# MainBlock-Inputs.net
KiCad netlist of a schematic drawn in Altium Designer
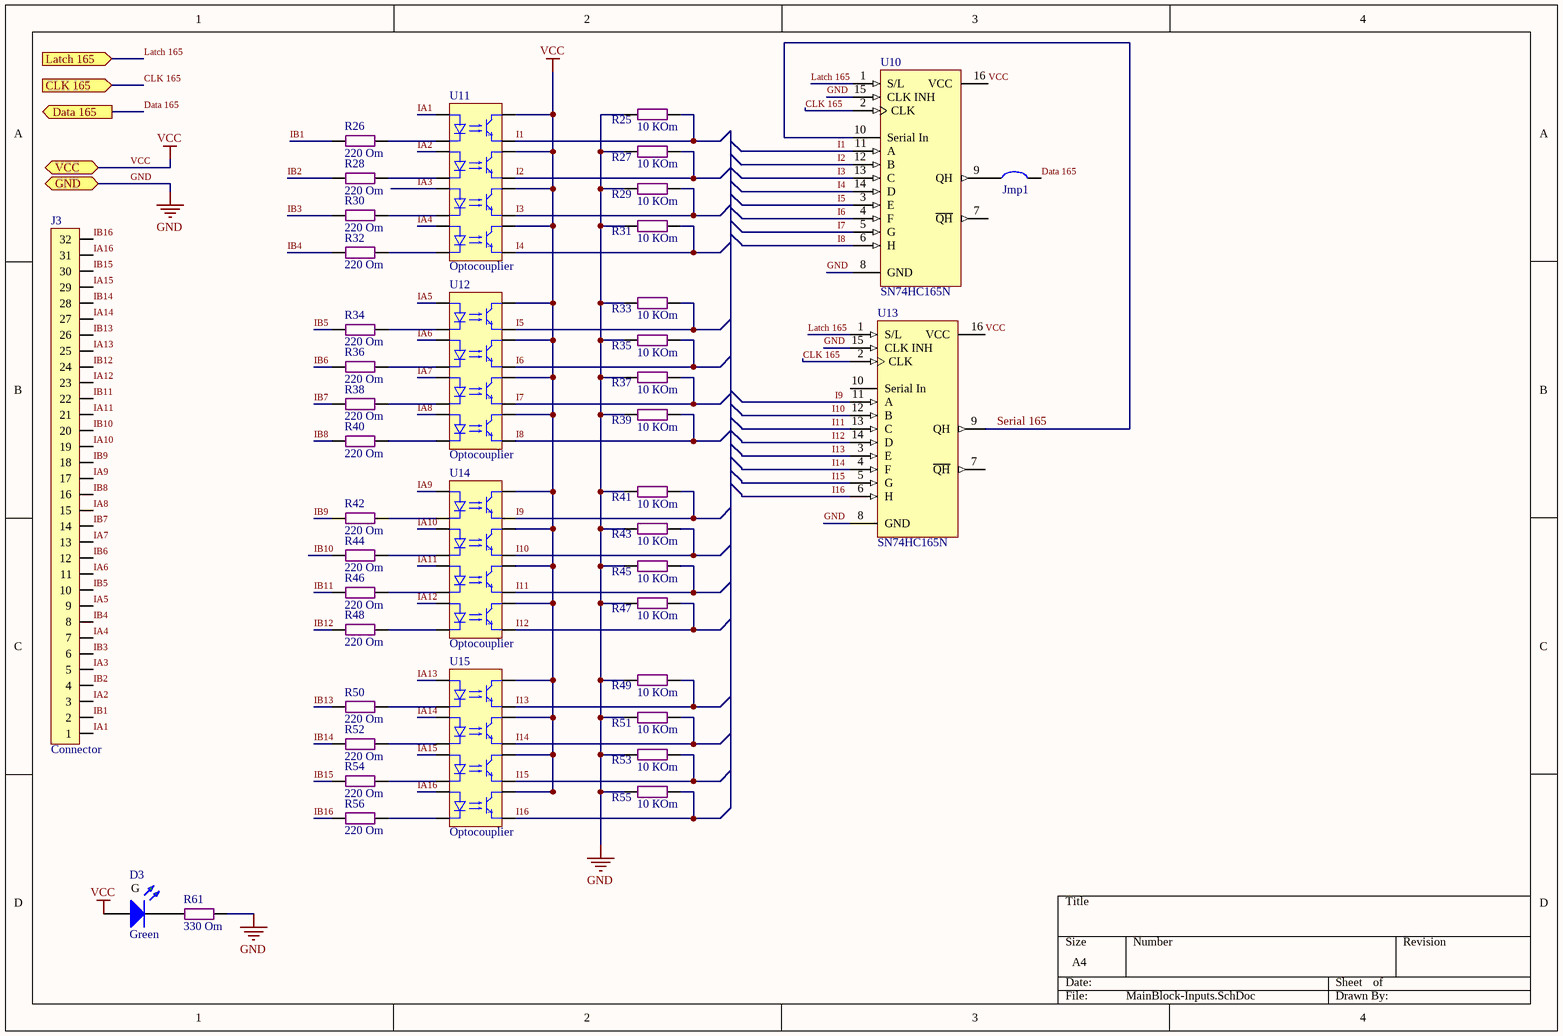
[diagram p0: MainBlock-Inputs.SchDoc]

(export (version "E")
  (design (tool "Eeschema 10.0.6"))
  (components
    (comp (ref "D3")
      (value "Green")
      (footprint "LED:LED SMD 0805 Green")
      (description "?2v ?20mA")
      (libsource (lib "LED") (part "Led SMD 0805 Green"))
    )
    (comp (ref "J3")
      (value "Connector")
      (footprint "bj Lib:LINE 2.54 x 16D")
      (description "32pin Connector")
      (libsource (lib "ss_ServersControl") (part "Connector Dbl ( 32 pin )"))
    )
    (comp (ref "Jmp1")
      (value "Jumper")
      (footprint "bj Lib:Jumper S 13x4")
      (libsource (lib "ss_ServersControl") (part "Jumper"))
    )
    (comp (ref "R25")
      (value "10 КOm")
      (footprint "SMD 0603 (1608)")
      (libsource (lib "ss_ServersControl") (part "Resistor"))
    )
    (comp (ref "R26")
      (value "220 Om")
      (footprint "bj Lib:SMD 1206 (3216)")
      (libsource (lib "ss_ServersControl") (part "Resistor"))
    )
    (comp (ref "R27")
      (value "10 КOm")
      (footprint "SMD 0603 (1608)")
      (libsource (lib "ss_ServersControl") (part "Resistor"))
    )
    (comp (ref "R28")
      (value "220 Om")
      (footprint "bj Lib:SMD 1206 (3216)")
      (libsource (lib "ss_ServersControl") (part "Resistor"))
    )
    (comp (ref "R29")
      (value "10 КOm")
      (footprint "SMD 0603 (1608)")
      (libsource (lib "ss_ServersControl") (part "Resistor"))
    )
    (comp (ref "R30")
      (value "220 Om")
      (footprint "bj Lib:SMD 1206 (3216)")
      (libsource (lib "ss_ServersControl") (part "Resistor"))
    )
    (comp (ref "R31")
      (value "10 КOm")
      (footprint "SMD 0603 (1608)")
      (libsource (lib "ss_ServersControl") (part "Resistor"))
    )
    (comp (ref "R32")
      (value "220 Om")
      (footprint "bj Lib:SMD 1206 (3216)")
      (libsource (lib "ss_ServersControl") (part "Resistor"))
    )
    (comp (ref "R33")
      (value "10 КOm")
      (footprint "SMD 0603 (1608)")
      (libsource (lib "ss_ServersControl") (part "Resistor"))
    )
    (comp (ref "R34")
      (value "220 Om")
      (footprint "bj Lib:SMD 1206 (3216)")
      (libsource (lib "ss_ServersControl") (part "Resistor"))
    )
    (comp (ref "R35")
      (value "10 КOm")
      (footprint "SMD 0603 (1608)")
      (libsource (lib "ss_ServersControl") (part "Resistor"))
    )
    (comp (ref "R36")
      (value "220 Om")
      (footprint "bj Lib:SMD 1206 (3216)")
      (libsource (lib "ss_ServersControl") (part "Resistor"))
    )
    (comp (ref "R37")
      (value "10 КOm")
      (footprint "SMD 0603 (1608)")
      (libsource (lib "ss_ServersControl") (part "Resistor"))
    )
    (comp (ref "R38")
      (value "220 Om")
      (footprint "bj Lib:SMD 1206 (3216)")
      (libsource (lib "ss_ServersControl") (part "Resistor"))
    )
    (comp (ref "R39")
      (value "10 КOm")
      (footprint "SMD 0603 (1608)")
      (libsource (lib "ss_ServersControl") (part "Resistor"))
    )
    (comp (ref "R40")
      (value "220 Om")
      (footprint "bj Lib:SMD 1206 (3216)")
      (libsource (lib "ss_ServersControl") (part "Resistor"))
    )
    (comp (ref "R41")
      (value "10 КOm")
      (footprint "SMD 0603 (1608)")
      (libsource (lib "ss_ServersControl") (part "Resistor"))
    )
    (comp (ref "R42")
      (value "220 Om")
      (footprint "Res p7.62 (4p)")
      (libsource (lib "ss_ServersControl") (part "Resistor"))
    )
    (comp (ref "R43")
      (value "10 КOm")
      (footprint "SMD 0603 (1608)")
      (libsource (lib "ss_ServersControl") (part "Resistor"))
    )
    (comp (ref "R44")
      (value "220 Om")
      (footprint "Res p7.62 (4p)")
      (libsource (lib "ss_ServersControl") (part "Resistor"))
    )
    (comp (ref "R45")
      (value "10 КOm")
      (footprint "SMD 0603 (1608)")
      (libsource (lib "ss_ServersControl") (part "Resistor"))
    )
    (comp (ref "R46")
      (value "220 Om")
      (footprint "Res p7.62 (4p)")
      (libsource (lib "ss_ServersControl") (part "Resistor"))
    )
    (comp (ref "R47")
      (value "10 КOm")
      (footprint "SMD 0603 (1608)")
      (libsource (lib "ss_ServersControl") (part "Resistor"))
    )
    (comp (ref "R48")
      (value "220 Om")
      (footprint "Res p7.62 (4p)")
      (libsource (lib "ss_ServersControl") (part "Resistor"))
    )
    (comp (ref "R49")
      (value "10 КOm")
      (footprint "SMD 0603 (1608)")
      (libsource (lib "ss_ServersControl") (part "Resistor"))
    )
    (comp (ref "R50")
      (value "220 Om")
      (footprint "bj Lib:SMD 1206 (3216)")
      (libsource (lib "ss_ServersControl") (part "Resistor"))
    )
    (comp (ref "R51")
      (value "10 КOm")
      (footprint "SMD 0603 (1608)")
      (libsource (lib "ss_ServersControl") (part "Resistor"))
    )
    (comp (ref "R52")
      (value "220 Om")
      (footprint "bj Lib:SMD 1206 (3216)")
      (libsource (lib "ss_ServersControl") (part "Resistor"))
    )
    (comp (ref "R53")
      (value "10 КOm")
      (footprint "SMD 0603 (1608)")
      (libsource (lib "ss_ServersControl") (part "Resistor"))
    )
    (comp (ref "R54")
      (value "220 Om")
      (footprint "bj Lib:SMD 1206 (3216)")
      (libsource (lib "ss_ServersControl") (part "Resistor"))
    )
    (comp (ref "R55")
      (value "10 КOm")
      (footprint "SMD 0603 (1608)")
      (libsource (lib "ss_ServersControl") (part "Resistor"))
    )
    (comp (ref "R56")
      (value "220 Om")
      (footprint "bj Lib:SMD 1206 (3216)")
      (libsource (lib "ss_ServersControl") (part "Resistor"))
    )
    (comp (ref "R61")
      (value "330 Om")
      (footprint "bj Lib:SMD 0603 (1608)")
      (libsource (lib "ss_ServersControl") (part "Resistor"))
    )
    (comp (ref "U10")
      (value "SN74HC165N")
      (footprint "bj Lib:DIP16")
      (description "8-Bit Parallel-Load Shift Register")
      (fields (field (name "PUBLISHER") "Altium Limited"))
      (libsource (lib "ss_ServersControl") (part "SN74HC165N"))
    )
    (comp (ref "U11")
      (value "Optocouplier")
      (footprint "bj Lib:DIP16")
      (description "4x channel")
      (libsource (lib "bj Lib") (part "Optocouplier 4x"))
    )
    (comp (ref "U12")
      (value "Optocouplier")
      (footprint "bj Lib:DIP16")
      (description "4x channel")
      (libsource (lib "bj Lib") (part "Optocouplier 4x"))
    )
    (comp (ref "U13")
      (value "SN74HC165N")
      (footprint "bj Lib:DIP16")
      (description "8-Bit Parallel-Load Shift Register")
      (fields (field (name "PUBLISHER") "Altium Limited"))
      (libsource (lib "ss_ServersControl") (part "SN74HC165N"))
    )
    (comp (ref "U14")
      (value "Optocouplier")
      (footprint "bj Lib:DIP16")
      (description "4x channel")
      (libsource (lib "bj Lib") (part "Optocouplier 4x"))
    )
    (comp (ref "U15")
      (value "Optocouplier")
      (footprint "bj Lib:DIP16")
      (description "4x channel")
      (libsource (lib "bj Lib") (part "Optocouplier 4x"))
    )
  )
  (nets
    (net (code "1") (name "/CLK 165") (class "Default")
      (node (ref "U10") (pin "2") (pinfunction "CLK_2") (pintype "input"))
      (node (ref "U13") (pin "2") (pinfunction "CLK_2") (pintype "input"))
    )
    (net (code "2") (name "/Data 165") (class "Default")
      (node (ref "Jmp1") (pin "2") (pinfunction "2_2") (pintype "passive"))
    )
    (net (code "3") (name "/I1") (class "Default")
      (node (ref "R25") (pin "2") (pinfunction "2_2") (pintype "passive"))
      (node (ref "U10") (pin "11") (pinfunction "A_11") (pintype "input"))
      (node (ref "U11") (pin "15") (pinfunction "15_15") (pintype "passive"))
    )
    (net (code "4") (name "/I2") (class "Default")
      (node (ref "R27") (pin "2") (pinfunction "2_2") (pintype "passive"))
      (node (ref "U10") (pin "12") (pinfunction "B_12") (pintype "input"))
      (node (ref "U11") (pin "13") (pinfunction "13_13") (pintype "passive"))
    )
    (net (code "5") (name "/I3") (class "Default")
      (node (ref "R29") (pin "2") (pinfunction "2_2") (pintype "passive"))
      (node (ref "U10") (pin "13") (pinfunction "C_13") (pintype "input"))
      (node (ref "U11") (pin "11") (pinfunction "11_11") (pintype "passive"))
    )
    (net (code "6") (name "/I4") (class "Default")
      (node (ref "R31") (pin "2") (pinfunction "2_2") (pintype "passive"))
      (node (ref "U10") (pin "14") (pinfunction "D_14") (pintype "input"))
      (node (ref "U11") (pin "9") (pinfunction "9_9") (pintype "passive"))
    )
    (net (code "7") (name "/I5") (class "Default")
      (node (ref "R33") (pin "2") (pinfunction "2_2") (pintype "passive"))
      (node (ref "U10") (pin "3") (pinfunction "E_3") (pintype "input"))
      (node (ref "U12") (pin "15") (pinfunction "15_15") (pintype "passive"))
    )
    (net (code "8") (name "/I6") (class "Default")
      (node (ref "R35") (pin "2") (pinfunction "2_2") (pintype "passive"))
      (node (ref "U10") (pin "4") (pinfunction "F_4") (pintype "input"))
      (node (ref "U12") (pin "13") (pinfunction "13_13") (pintype "passive"))
    )
    (net (code "9") (name "/I7") (class "Default")
      (node (ref "R37") (pin "2") (pinfunction "2_2") (pintype "passive"))
      (node (ref "U10") (pin "5") (pinfunction "G_5") (pintype "input"))
      (node (ref "U12") (pin "11") (pinfunction "11_11") (pintype "passive"))
    )
    (net (code "10") (name "/I8") (class "Default")
      (node (ref "R39") (pin "2") (pinfunction "2_2") (pintype "passive"))
      (node (ref "U10") (pin "6") (pinfunction "H_6") (pintype "input"))
      (node (ref "U12") (pin "9") (pinfunction "9_9") (pintype "passive"))
    )
    (net (code "11") (name "/I9") (class "Default")
      (node (ref "R41") (pin "2") (pinfunction "2_2") (pintype "passive"))
      (node (ref "U13") (pin "11") (pinfunction "A_11") (pintype "input"))
      (node (ref "U14") (pin "15") (pinfunction "15_15") (pintype "passive"))
    )
    (net (code "12") (name "/I10") (class "Default")
      (node (ref "R43") (pin "2") (pinfunction "2_2") (pintype "passive"))
      (node (ref "U13") (pin "12") (pinfunction "B_12") (pintype "input"))
      (node (ref "U14") (pin "13") (pinfunction "13_13") (pintype "passive"))
    )
    (net (code "13") (name "/I11") (class "Default")
      (node (ref "R45") (pin "2") (pinfunction "2_2") (pintype "passive"))
      (node (ref "U13") (pin "13") (pinfunction "C_13") (pintype "input"))
      (node (ref "U14") (pin "11") (pinfunction "11_11") (pintype "passive"))
    )
    (net (code "14") (name "/I12") (class "Default")
      (node (ref "R47") (pin "2") (pinfunction "2_2") (pintype "passive"))
      (node (ref "U13") (pin "14") (pinfunction "D_14") (pintype "input"))
      (node (ref "U14") (pin "9") (pinfunction "9_9") (pintype "passive"))
    )
    (net (code "15") (name "/I13") (class "Default")
      (node (ref "R49") (pin "2") (pinfunction "2_2") (pintype "passive"))
      (node (ref "U13") (pin "3") (pinfunction "E_3") (pintype "input"))
      (node (ref "U15") (pin "15") (pinfunction "15_15") (pintype "passive"))
    )
    (net (code "16") (name "/I14") (class "Default")
      (node (ref "R51") (pin "2") (pinfunction "2_2") (pintype "passive"))
      (node (ref "U13") (pin "4") (pinfunction "F_4") (pintype "input"))
      (node (ref "U15") (pin "13") (pinfunction "13_13") (pintype "passive"))
    )
    (net (code "17") (name "/I15") (class "Default")
      (node (ref "R53") (pin "2") (pinfunction "2_2") (pintype "passive"))
      (node (ref "U13") (pin "5") (pinfunction "G_5") (pintype "input"))
      (node (ref "U15") (pin "11") (pinfunction "11_11") (pintype "passive"))
    )
    (net (code "18") (name "/I16") (class "Default")
      (node (ref "R55") (pin "2") (pinfunction "2_2") (pintype "passive"))
      (node (ref "U13") (pin "6") (pinfunction "H_6") (pintype "input"))
      (node (ref "U15") (pin "9") (pinfunction "9_9") (pintype "passive"))
    )
    (net (code "19") (name "/IA1") (class "Default")
      (node (ref "J3") (pin "1") (pinfunction "1_1") (pintype "passive"))
      (node (ref "U11") (pin "1") (pinfunction "1_1") (pintype "passive"))
    )
    (net (code "20") (name "/IA2") (class "Default")
      (node (ref "J3") (pin "3") (pinfunction "3_3") (pintype "passive"))
      (node (ref "U11") (pin "3") (pinfunction "3_3") (pintype "passive"))
    )
    (net (code "21") (name "/IA3") (class "Default")
      (node (ref "J3") (pin "5") (pinfunction "5_5") (pintype "passive"))
      (node (ref "U11") (pin "5") (pinfunction "5_5") (pintype "passive"))
    )
    (net (code "22") (name "/IA4") (class "Default")
      (node (ref "J3") (pin "7") (pinfunction "7_7") (pintype "passive"))
      (node (ref "U11") (pin "7") (pinfunction "7_7") (pintype "passive"))
    )
    (net (code "23") (name "/IA5") (class "Default")
      (node (ref "J3") (pin "9") (pinfunction "9_9") (pintype "passive"))
      (node (ref "U12") (pin "1") (pinfunction "1_1") (pintype "passive"))
    )
    (net (code "24") (name "/IA6") (class "Default")
      (node (ref "J3") (pin "11") (pinfunction "11_11") (pintype "passive"))
      (node (ref "U12") (pin "3") (pinfunction "3_3") (pintype "passive"))
    )
    (net (code "25") (name "/IA7") (class "Default")
      (node (ref "J3") (pin "13") (pinfunction "13_13") (pintype "passive"))
      (node (ref "U12") (pin "5") (pinfunction "5_5") (pintype "passive"))
    )
    (net (code "26") (name "/IA8") (class "Default")
      (node (ref "J3") (pin "15") (pinfunction "15_15") (pintype "passive"))
      (node (ref "U12") (pin "7") (pinfunction "7_7") (pintype "passive"))
    )
    (net (code "27") (name "/IA9") (class "Default")
      (node (ref "J3") (pin "17") (pinfunction "17_17") (pintype "passive"))
      (node (ref "U14") (pin "1") (pinfunction "1_1") (pintype "passive"))
    )
    (net (code "28") (name "/IA10") (class "Default")
      (node (ref "J3") (pin "19") (pinfunction "19_19") (pintype "passive"))
      (node (ref "U14") (pin "3") (pinfunction "3_3") (pintype "passive"))
    )
    (net (code "29") (name "/IA11") (class "Default")
      (node (ref "J3") (pin "21") (pinfunction "21_21") (pintype "passive"))
      (node (ref "U14") (pin "5") (pinfunction "5_5") (pintype "passive"))
    )
    (net (code "30") (name "/IA12") (class "Default")
      (node (ref "J3") (pin "23") (pinfunction "23_23") (pintype "passive"))
      (node (ref "U14") (pin "7") (pinfunction "7_7") (pintype "passive"))
    )
    (net (code "31") (name "/IA13") (class "Default")
      (node (ref "J3") (pin "25") (pinfunction "25_25") (pintype "passive"))
      (node (ref "U15") (pin "1") (pinfunction "1_1") (pintype "passive"))
    )
    (net (code "32") (name "/IA14") (class "Default")
      (node (ref "J3") (pin "27") (pinfunction "27_27") (pintype "passive"))
      (node (ref "U15") (pin "3") (pinfunction "3_3") (pintype "passive"))
    )
    (net (code "33") (name "/IA15") (class "Default")
      (node (ref "J3") (pin "29") (pinfunction "29_29") (pintype "passive"))
      (node (ref "U15") (pin "5") (pinfunction "5_5") (pintype "passive"))
    )
    (net (code "34") (name "/IA16") (class "Default")
      (node (ref "J3") (pin "31") (pinfunction "31_31") (pintype "passive"))
      (node (ref "U15") (pin "7") (pinfunction "7_7") (pintype "passive"))
    )
    (net (code "35") (name "/IB1") (class "Default")
      (node (ref "J3") (pin "2") (pinfunction "2_2") (pintype "passive"))
      (node (ref "R26") (pin "1") (pinfunction "1_1") (pintype "passive"))
    )
    (net (code "36") (name "/IB2") (class "Default")
      (node (ref "J3") (pin "4") (pinfunction "4_4") (pintype "passive"))
      (node (ref "R28") (pin "1") (pinfunction "1_1") (pintype "passive"))
    )
    (net (code "37") (name "/IB3") (class "Default")
      (node (ref "J3") (pin "6") (pinfunction "6_6") (pintype "passive"))
      (node (ref "R30") (pin "1") (pinfunction "1_1") (pintype "passive"))
    )
    (net (code "38") (name "/IB4") (class "Default")
      (node (ref "J3") (pin "8") (pinfunction "8_8") (pintype "passive"))
      (node (ref "R32") (pin "1") (pinfunction "1_1") (pintype "passive"))
    )
    (net (code "39") (name "/IB5") (class "Default")
      (node (ref "J3") (pin "10") (pinfunction "10_10") (pintype "passive"))
      (node (ref "R34") (pin "1") (pinfunction "1_1") (pintype "passive"))
    )
    (net (code "40") (name "/IB6") (class "Default")
      (node (ref "J3") (pin "12") (pinfunction "12_12") (pintype "passive"))
      (node (ref "R36") (pin "1") (pinfunction "1_1") (pintype "passive"))
    )
    (net (code "41") (name "/IB7") (class "Default")
      (node (ref "J3") (pin "14") (pinfunction "14_14") (pintype "passive"))
      (node (ref "R38") (pin "1") (pinfunction "1_1") (pintype "passive"))
    )
    (net (code "42") (name "/IB8") (class "Default")
      (node (ref "J3") (pin "16") (pinfunction "16_16") (pintype "passive"))
      (node (ref "R40") (pin "1") (pinfunction "1_1") (pintype "passive"))
    )
    (net (code "43") (name "/IB9") (class "Default")
      (node (ref "J3") (pin "18") (pinfunction "18_18") (pintype "passive"))
      (node (ref "R42") (pin "1") (pinfunction "1_1") (pintype "passive"))
    )
    (net (code "44") (name "/IB10") (class "Default")
      (node (ref "J3") (pin "20") (pinfunction "20_20") (pintype "passive"))
      (node (ref "R44") (pin "1") (pinfunction "1_1") (pintype "passive"))
    )
    (net (code "45") (name "/IB11") (class "Default")
      (node (ref "J3") (pin "22") (pinfunction "22_22") (pintype "passive"))
      (node (ref "R46") (pin "1") (pinfunction "1_1") (pintype "passive"))
    )
    (net (code "46") (name "/IB12") (class "Default")
      (node (ref "J3") (pin "24") (pinfunction "24_24") (pintype "passive"))
      (node (ref "R48") (pin "1") (pinfunction "1_1") (pintype "passive"))
    )
    (net (code "47") (name "/IB13") (class "Default")
      (node (ref "J3") (pin "26") (pinfunction "26_26") (pintype "passive"))
      (node (ref "R50") (pin "1") (pinfunction "1_1") (pintype "passive"))
    )
    (net (code "48") (name "/IB14") (class "Default")
      (node (ref "J3") (pin "28") (pinfunction "28_28") (pintype "passive"))
      (node (ref "R52") (pin "1") (pinfunction "1_1") (pintype "passive"))
    )
    (net (code "49") (name "/IB15") (class "Default")
      (node (ref "J3") (pin "30") (pinfunction "30_30") (pintype "passive"))
      (node (ref "R54") (pin "1") (pinfunction "1_1") (pintype "passive"))
    )
    (net (code "50") (name "/IB16") (class "Default")
      (node (ref "J3") (pin "32") (pinfunction "32_32") (pintype "passive"))
      (node (ref "R56") (pin "1") (pinfunction "1_1") (pintype "passive"))
    )
    (net (code "51") (name "/Latch 165") (class "Default")
      (node (ref "U10") (pin "1") (pinfunction "S/L_1") (pintype "input"))
      (node (ref "U13") (pin "1") (pinfunction "S/L_1") (pintype "input"))
    )
    (net (code "52") (name "/Serial 165") (class "Default")
      (node (ref "U10") (pin "10") (pinfunction "Serial_In_10") (pintype "passive"))
      (node (ref "U13") (pin "9") (pinfunction "QH_9") (pintype "output"))
    )
    (net (code "53") (name "GND") (class "Default")
      (node (ref "R25") (pin "1") (pinfunction "1_1") (pintype "passive"))
      (node (ref "R27") (pin "1") (pinfunction "1_1") (pintype "passive"))
      (node (ref "R29") (pin "1") (pinfunction "1_1") (pintype "passive"))
      (node (ref "R31") (pin "1") (pinfunction "1_1") (pintype "passive"))
      (node (ref "R33") (pin "1") (pinfunction "1_1") (pintype "passive"))
      (node (ref "R35") (pin "1") (pinfunction "1_1") (pintype "passive"))
      (node (ref "R37") (pin "1") (pinfunction "1_1") (pintype "passive"))
      (node (ref "R39") (pin "1") (pinfunction "1_1") (pintype "passive"))
      (node (ref "R41") (pin "1") (pinfunction "1_1") (pintype "passive"))
      (node (ref "R43") (pin "1") (pinfunction "1_1") (pintype "passive"))
      (node (ref "R45") (pin "1") (pinfunction "1_1") (pintype "passive"))
      (node (ref "R47") (pin "1") (pinfunction "1_1") (pintype "passive"))
      (node (ref "R49") (pin "1") (pinfunction "1_1") (pintype "passive"))
      (node (ref "R51") (pin "1") (pinfunction "1_1") (pintype "passive"))
      (node (ref "R53") (pin "1") (pinfunction "1_1") (pintype "passive"))
      (node (ref "R55") (pin "1") (pinfunction "1_1") (pintype "passive"))
      (node (ref "R61") (pin "2") (pinfunction "2_2") (pintype "passive"))
      (node (ref "U10") (pin "15") (pinfunction "CLK_INH_15") (pintype "input"))
      (node (ref "U10") (pin "8") (pinfunction "GND_8") (pintype "power_in"))
      (node (ref "U13") (pin "15") (pinfunction "CLK_INH_15") (pintype "input"))
      (node (ref "U13") (pin "8") (pinfunction "GND_8") (pintype "power_in"))
    )
    (net (code "54") (name "Net-(D3-PadK)") (class "Default")
      (node (ref "D3") (pin "K") (pinfunction "K_K") (pintype "passive"))
      (node (ref "R61") (pin "1") (pinfunction "1_1") (pintype "passive"))
    )
    (net (code "55") (name "Net-(R26-Pad2)") (class "Default")
      (node (ref "R26") (pin "2") (pinfunction "2_2") (pintype "passive"))
      (node (ref "U11") (pin "2") (pinfunction "2_2") (pintype "passive"))
    )
    (net (code "56") (name "Net-(R28-Pad2)") (class "Default")
      (node (ref "R28") (pin "2") (pinfunction "2_2") (pintype "passive"))
      (node (ref "U11") (pin "4") (pinfunction "4_4") (pintype "passive"))
    )
    (net (code "57") (name "Net-(R30-Pad2)") (class "Default")
      (node (ref "R30") (pin "2") (pinfunction "2_2") (pintype "passive"))
      (node (ref "U11") (pin "6") (pinfunction "6_6") (pintype "passive"))
    )
    (net (code "58") (name "Net-(R32-Pad2)") (class "Default")
      (node (ref "R32") (pin "2") (pinfunction "2_2") (pintype "passive"))
      (node (ref "U11") (pin "8") (pinfunction "8_8") (pintype "passive"))
    )
    (net (code "59") (name "Net-(R34-Pad2)") (class "Default")
      (node (ref "R34") (pin "2") (pinfunction "2_2") (pintype "passive"))
      (node (ref "U12") (pin "2") (pinfunction "2_2") (pintype "passive"))
    )
    (net (code "60") (name "Net-(R36-Pad2)") (class "Default")
      (node (ref "R36") (pin "2") (pinfunction "2_2") (pintype "passive"))
      (node (ref "U12") (pin "4") (pinfunction "4_4") (pintype "passive"))
    )
    (net (code "61") (name "Net-(R38-Pad2)") (class "Default")
      (node (ref "R38") (pin "2") (pinfunction "2_2") (pintype "passive"))
      (node (ref "U12") (pin "6") (pinfunction "6_6") (pintype "passive"))
    )
    (net (code "62") (name "Net-(R40-Pad2)") (class "Default")
      (node (ref "R40") (pin "2") (pinfunction "2_2") (pintype "passive"))
      (node (ref "U12") (pin "8") (pinfunction "8_8") (pintype "passive"))
    )
    (net (code "63") (name "Net-(R42-Pad2)") (class "Default")
      (node (ref "R42") (pin "2") (pinfunction "2_2") (pintype "passive"))
      (node (ref "U14") (pin "2") (pinfunction "2_2") (pintype "passive"))
    )
    (net (code "64") (name "Net-(R44-Pad2)") (class "Default")
      (node (ref "R44") (pin "2") (pinfunction "2_2") (pintype "passive"))
      (node (ref "U14") (pin "4") (pinfunction "4_4") (pintype "passive"))
    )
    (net (code "65") (name "Net-(R46-Pad2)") (class "Default")
      (node (ref "R46") (pin "2") (pinfunction "2_2") (pintype "passive"))
      (node (ref "U14") (pin "6") (pinfunction "6_6") (pintype "passive"))
    )
    (net (code "66") (name "Net-(R48-Pad2)") (class "Default")
      (node (ref "R48") (pin "2") (pinfunction "2_2") (pintype "passive"))
      (node (ref "U14") (pin "8") (pinfunction "8_8") (pintype "passive"))
    )
    (net (code "67") (name "Net-(R50-Pad2)") (class "Default")
      (node (ref "R50") (pin "2") (pinfunction "2_2") (pintype "passive"))
      (node (ref "U15") (pin "2") (pinfunction "2_2") (pintype "passive"))
    )
    (net (code "68") (name "Net-(R52-Pad2)") (class "Default")
      (node (ref "R52") (pin "2") (pinfunction "2_2") (pintype "passive"))
      (node (ref "U15") (pin "4") (pinfunction "4_4") (pintype "passive"))
    )
    (net (code "69") (name "Net-(R54-Pad2)") (class "Default")
      (node (ref "R54") (pin "2") (pinfunction "2_2") (pintype "passive"))
      (node (ref "U15") (pin "6") (pinfunction "6_6") (pintype "passive"))
    )
    (net (code "70") (name "Net-(R56-Pad2)") (class "Default")
      (node (ref "R56") (pin "2") (pinfunction "2_2") (pintype "passive"))
      (node (ref "U15") (pin "8") (pinfunction "8_8") (pintype "passive"))
    )
    (net (code "71") (name "Net-(U10-QH)") (class "Default")
      (node (ref "Jmp1") (pin "1") (pinfunction "1_1") (pintype "passive"))
      (node (ref "U10") (pin "9") (pinfunction "QH_9") (pintype "output"))
    )
    (net (code "72") (name "VCC") (class "Default")
      (node (ref "D3") (pin "A") (pinfunction "A_A") (pintype "passive"))
      (node (ref "U10") (pin "16") (pinfunction "VCC_16") (pintype "power_in"))
      (node (ref "U11") (pin "10") (pinfunction "10_10") (pintype "passive"))
      (node (ref "U11") (pin "12") (pinfunction "12_12") (pintype "passive"))
      (node (ref "U11") (pin "14") (pinfunction "14_14") (pintype "passive"))
      (node (ref "U11") (pin "16") (pinfunction "16_16") (pintype "passive"))
      (node (ref "U12") (pin "10") (pinfunction "10_10") (pintype "passive"))
      (node (ref "U12") (pin "12") (pinfunction "12_12") (pintype "passive"))
      (node (ref "U12") (pin "14") (pinfunction "14_14") (pintype "passive"))
      (node (ref "U12") (pin "16") (pinfunction "16_16") (pintype "passive"))
      (node (ref "U13") (pin "16") (pinfunction "VCC_16") (pintype "power_in"))
      (node (ref "U14") (pin "10") (pinfunction "10_10") (pintype "passive"))
      (node (ref "U14") (pin "12") (pinfunction "12_12") (pintype "passive"))
      (node (ref "U14") (pin "14") (pinfunction "14_14") (pintype "passive"))
      (node (ref "U14") (pin "16") (pinfunction "16_16") (pintype "passive"))
      (node (ref "U15") (pin "10") (pinfunction "10_10") (pintype "passive"))
      (node (ref "U15") (pin "12") (pinfunction "12_12") (pintype "passive"))
      (node (ref "U15") (pin "14") (pinfunction "14_14") (pintype "passive"))
      (node (ref "U15") (pin "16") (pinfunction "16_16") (pintype "passive"))
    )
    (net (code "73") (name "unconnected-(U10-~{QH}-Pad7)") (class "Default")
      (node (ref "U10") (pin "7") (pinfunction "~{QH}_7") (pintype "output"))
    )
    (net (code "74") (name "unconnected-(U13-Serial_In-Pad10)") (class "Default")
      (node (ref "U13") (pin "10") (pinfunction "Serial_In_10") (pintype "passive"))
    )
    (net (code "75") (name "unconnected-(U13-~{QH}-Pad7)") (class "Default")
      (node (ref "U13") (pin "7") (pinfunction "~{QH}_7") (pintype "output"))
    )
  )
)
